# SparkFun_Qwiic_ToF_Imager_-_VL53L5CX_-_M.net
KiCad netlist of a schematic drawn in EAGLE
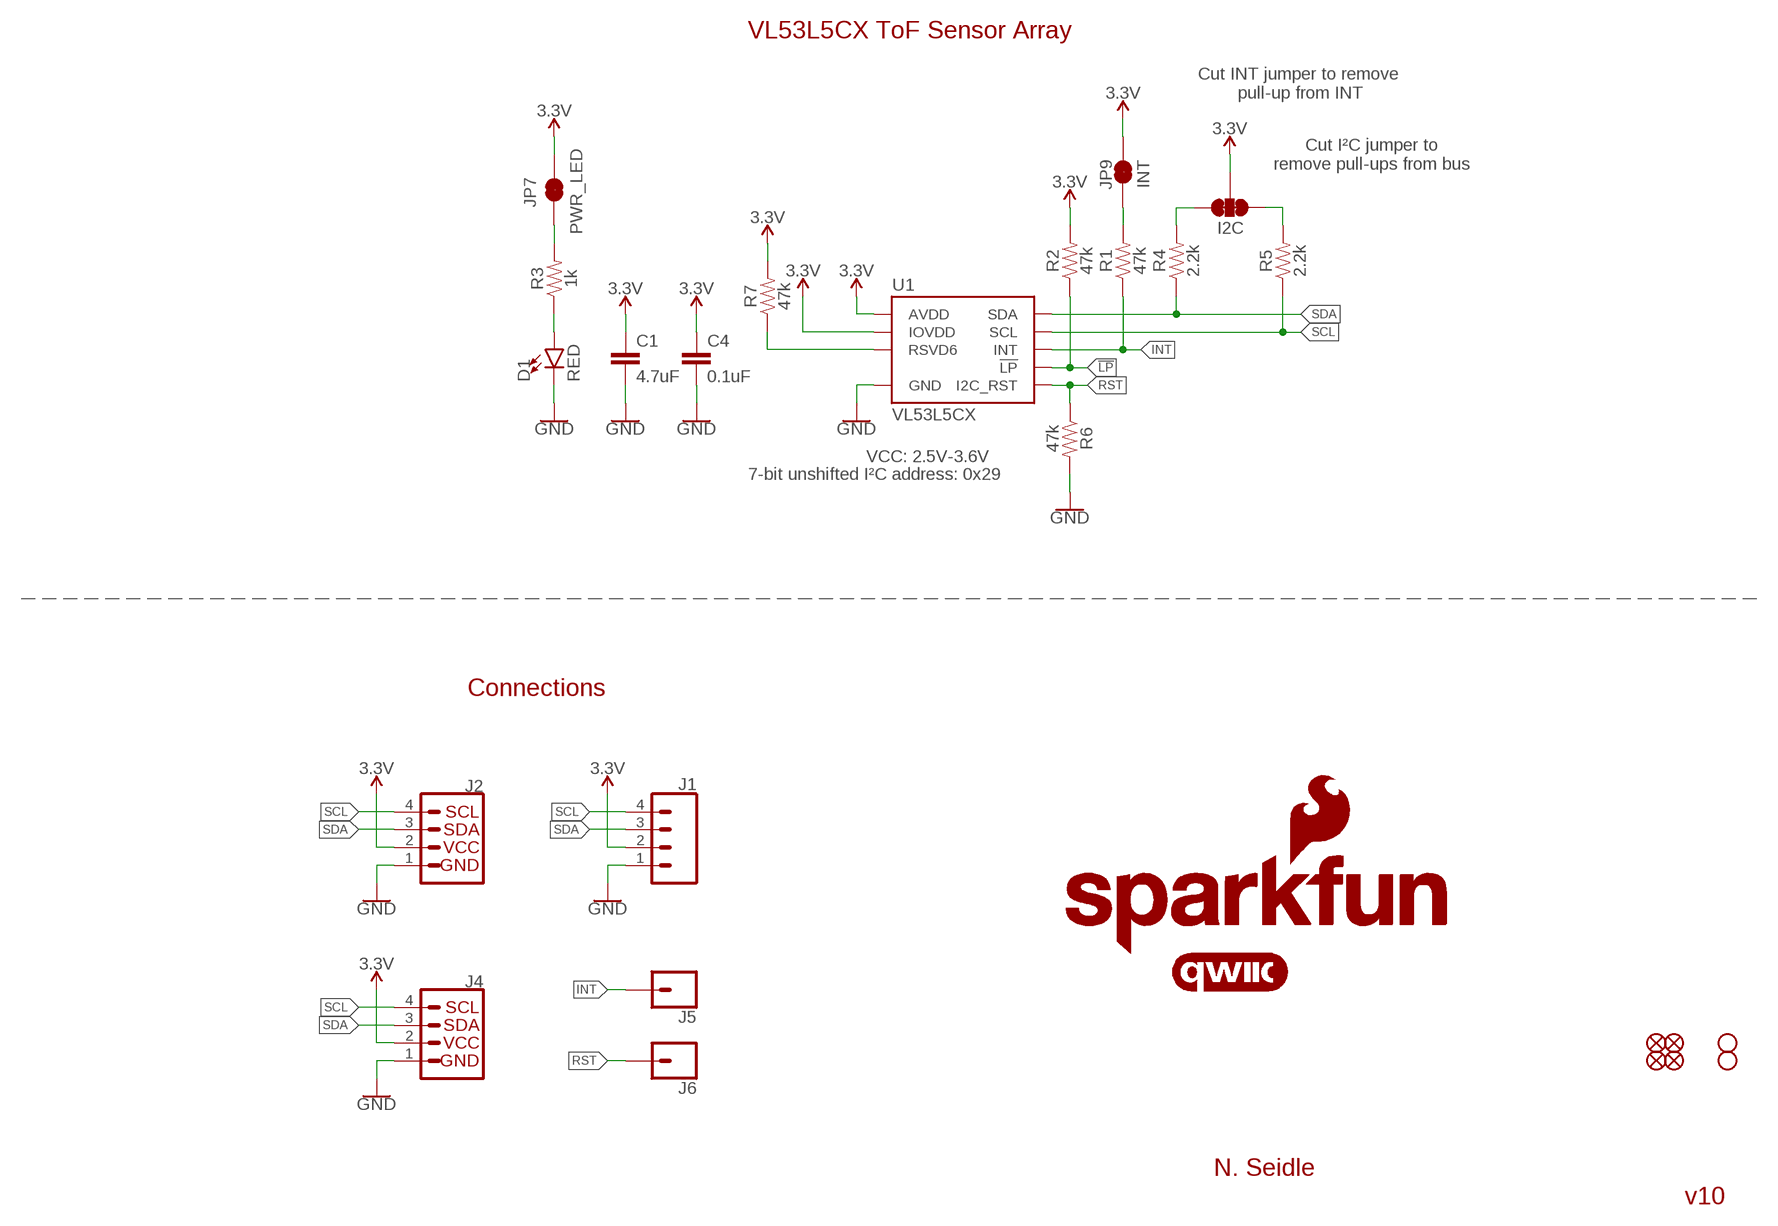
[diagram p0: schematic, sheet 1]

(export (version "E")
  (design (tool "Eeschema 10.0.6"))
  (components
    (comp (ref "C1")
      (value "4.7uF")
      (footprint "eagle-import:0402-TIGHT")
      (libsource (lib "eagle-import") (part "4.7UF-0402_TIGHT-6.3V-20%-X5R"))
    )
    (comp (ref "C4")
      (value "0.1uF")
      (footprint "eagle-import:0402-TIGHT")
      (libsource (lib "eagle-import") (part "0.1UF-0402T-6.3V-10%-X7R"))
    )
    (comp (ref "D1")
      (value "RED")
      (footprint "eagle-import:LED-0603")
      (libsource (lib "eagle-import") (part "LED-RED0603"))
    )
    (comp (ref "I2C")
      (value "JUMPER-SMT_3_2-NC_TRACE_SILK")
      (footprint "eagle-import:SMT-JUMPER_3_2-NC_TRACE_SILK")
      (libsource (lib "eagle-import") (part "JUMPER-SMT_3_2-NC_TRACE_SILK"))
    )
    (comp (ref "J1")
      (value "CONN_041X04_NO_SILK")
      (footprint "eagle-import:1X04_NO_SILK")
      (libsource (lib "eagle-import") (part "CONN_041X04_NO_SILK"))
    )
    (comp (ref "J2")
      (value "Vertical Qwiic Connector")
      (footprint "eagle-import:JST04_1MM_VERT")
      (libsource (lib "eagle-import") (part "QWIIC_CONNECTOR"))
    )
    (comp (ref "J4")
      (value "Vertical Qwiic Connector")
      (footprint "eagle-import:JST04_1MM_VERT")
      (libsource (lib "eagle-import") (part "QWIIC_CONNECTOR"))
    )
    (comp (ref "J5")
      (value "CONN_01PTH_NO_SILK_YES_STOP")
      (footprint "eagle-import:1X01_NO_SILK")
      (libsource (lib "eagle-import") (part "CONN_01PTH_NO_SILK_YES_STOP"))
    )
    (comp (ref "J6")
      (value "CONN_01PTH_NO_SILK_YES_STOP")
      (footprint "eagle-import:1X01_NO_SILK")
      (libsource (lib "eagle-import") (part "CONN_01PTH_NO_SILK_YES_STOP"))
    )
    (comp (ref "JP1")
      (value "FIDUCIALUFIDUCIAL")
      (footprint "eagle-import:FIDUCIAL-MICRO")
      (libsource (lib "eagle-import") (part "FIDUCIALUFIDUCIAL"))
    )
    (comp (ref "JP2")
      (value "FIDUCIALUFIDUCIAL")
      (footprint "eagle-import:FIDUCIAL-MICRO")
      (libsource (lib "eagle-import") (part "FIDUCIALUFIDUCIAL"))
    )
    (comp (ref "JP5")
      (value "FIDUCIALUFIDUCIAL")
      (footprint "eagle-import:FIDUCIAL-MICRO")
      (libsource (lib "eagle-import") (part "FIDUCIALUFIDUCIAL"))
    )
    (comp (ref "JP6")
      (value "FIDUCIALUFIDUCIAL")
      (footprint "eagle-import:FIDUCIAL-MICRO")
      (libsource (lib "eagle-import") (part "FIDUCIALUFIDUCIAL"))
    )
    (comp (ref "JP7")
      (value "PWR_LED")
      (footprint "eagle-import:SMT-JUMPER_2_NC_TRACE_SILK")
      (libsource (lib "eagle-import") (part "JUMPER-SMT_2_NC_TRACE_SILK"))
    )
    (comp (ref "JP9")
      (value "INT")
      (footprint "eagle-import:SMT-JUMPER_2_NC_TRACE_SILK")
      (libsource (lib "eagle-import") (part "JUMPER-SMT_2_NC_TRACE_SILK"))
    )
    (comp (ref "JP10")
      (value "STAND-OFF")
      (footprint "eagle-import:STAND-OFF")
      (libsource (lib "eagle-import") (part "STAND-OFF"))
    )
    (comp (ref "JP11")
      (value "STAND-OFF")
      (footprint "eagle-import:STAND-OFF")
      (libsource (lib "eagle-import") (part "STAND-OFF"))
    )
    (comp (ref "LOGO1")
      (value "SFE_LOGO_NAME_FLAME8_MM")
      (footprint "eagle-import:SFE_LOGO_NAME_FLAME_8MM")
      (libsource (lib "eagle-import") (part "SFE_LOGO_NAME_FLAME8_MM"))
    )
    (comp (ref "LOGO3")
      (value "QWIIC_LOGO_CONNECTOR")
      (footprint "eagle-import:QWIIC_5.5MM")
      (libsource (lib "eagle-import") (part "QWIIC_LOGO_CONNECTOR"))
    )
    (comp (ref "LOGO4")
      (value "SFE_LOGO_NAME6_MM")
      (footprint "eagle-import:SFE_LOGO_NAME_6MM")
      (libsource (lib "eagle-import") (part "SFE_LOGO_NAME6_MM"))
    )
    (comp (ref "R1")
      (value "47k")
      (footprint "eagle-import:0402-TIGHT")
      (libsource (lib "eagle-import") (part "47KOHM-0402-1/10W-1%"))
    )
    (comp (ref "R2")
      (value "47k")
      (footprint "eagle-import:0402-TIGHT")
      (libsource (lib "eagle-import") (part "47KOHM-0402-1/10W-1%"))
    )
    (comp (ref "R3")
      (value "1k")
      (footprint "eagle-import:0402-TIGHT")
      (libsource (lib "eagle-import") (part "1KOHM-0402T-1/16W-1%"))
    )
    (comp (ref "R4")
      (value "2.2k")
      (footprint "eagle-import:0402-TIGHT")
      (libsource (lib "eagle-import") (part "2.2KOHM-0402T-1/16W-1%"))
    )
    (comp (ref "R5")
      (value "2.2k")
      (footprint "eagle-import:0402-TIGHT")
      (libsource (lib "eagle-import") (part "2.2KOHM-0402T-1/16W-1%"))
    )
    (comp (ref "R6")
      (value "47k")
      (footprint "eagle-import:0402-TIGHT")
      (libsource (lib "eagle-import") (part "47KOHM-0402-1/10W-1%"))
    )
    (comp (ref "R7")
      (value "47k")
      (footprint "eagle-import:0402-TIGHT")
      (libsource (lib "eagle-import") (part "47KOHM-0402-1/10W-1%"))
    )
    (comp (ref "U1")
      (value "VL53L5CX")
      (footprint "eagle-import:VL53L5CX")
      (libsource (lib "eagle-import") (part "VL53L5CX"))
    )
  )
  (nets
    (net (code "1") (name "/~{LP}") (class "Default")
      (node (ref "R2") (pin "1") (pinfunction "1_1") (pintype "passive"))
      (node (ref "U1") (pin "A5") (pinfunction "~{LP}_A5") (pintype "bidirectional"))
    )
    (net (code "2") (name "3.3V") (class "Default")
      (node (ref "C1") (pin "1") (pinfunction "1_1") (pintype "passive"))
      (node (ref "C4") (pin "1") (pinfunction "1_1") (pintype "passive"))
      (node (ref "I2C") (pin "2") (pinfunction "2_2") (pintype "passive"))
      (node (ref "J1") (pin "2") (pinfunction "2_2") (pintype "passive"))
      (node (ref "J2") (pin "2") (pinfunction "2_2") (pintype "power_in"))
      (node (ref "J4") (pin "2") (pinfunction "2_2") (pintype "power_in"))
      (node (ref "JP7") (pin "2") (pinfunction "2_2") (pintype "passive"))
      (node (ref "JP9") (pin "2") (pinfunction "2_2") (pintype "passive"))
      (node (ref "R2") (pin "2") (pinfunction "2_2") (pintype "passive"))
      (node (ref "R7") (pin "2") (pinfunction "2_2") (pintype "passive"))
      (node (ref "U1") (pin "A4") (pinfunction "IOVDD_A4") (pintype "bidirectional"))
      (node (ref "U1") (pin "B1") (pinfunction "AVDD_B1") (pintype "bidirectional"))
      (node (ref "U1") (pin "B7") (pinfunction "AVDD_B7") (pintype "bidirectional"))
    )
    (net (code "3") (name "GND") (class "Default")
      (node (ref "C1") (pin "2") (pinfunction "2_2") (pintype "passive"))
      (node (ref "C4") (pin "2") (pinfunction "2_2") (pintype "passive"))
      (node (ref "D1") (pin "C") (pinfunction "C_C") (pintype "passive"))
      (node (ref "J1") (pin "1") (pinfunction "1_1") (pintype "passive"))
      (node (ref "J2") (pin "1") (pinfunction "1_1") (pintype "power_in"))
      (node (ref "J4") (pin "1") (pinfunction "1_1") (pintype "power_in"))
      (node (ref "R6") (pin "2") (pinfunction "2_2") (pintype "passive"))
      (node (ref "U1") (pin "A2") (pinfunction "GND_A2") (pintype "bidirectional"))
      (node (ref "U1") (pin "A6") (pinfunction "GND_A6") (pintype "bidirectional"))
      (node (ref "U1") (pin "A7") (pinfunction "GND_A7") (pintype "bidirectional"))
      (node (ref "U1") (pin "B4") (pinfunction "GND_B4") (pintype "bidirectional"))
      (node (ref "U1") (pin "C1") (pinfunction "GND_C1") (pintype "bidirectional"))
      (node (ref "U1") (pin "C6") (pinfunction "GND_C6") (pintype "bidirectional"))
      (node (ref "U1") (pin "C7") (pinfunction "GND_C7") (pintype "bidirectional"))
    )
    (net (code "4") (name "INT") (class "Default")
      (node (ref "J5") (pin "1") (pinfunction "1_1") (pintype "passive"))
      (node (ref "R1") (pin "1") (pinfunction "1_1") (pintype "passive"))
      (node (ref "U1") (pin "A3") (pinfunction "INT_A3") (pintype "bidirectional"))
    )
    (net (code "5") (name "Net-(D1-PadA)") (class "Default")
      (node (ref "D1") (pin "A") (pinfunction "A_A") (pintype "passive"))
      (node (ref "R3") (pin "1") (pinfunction "1_1") (pintype "passive"))
    )
    (net (code "6") (name "Net-(I2C-Pad1)") (class "Default")
      (node (ref "I2C") (pin "1") (pinfunction "1_1") (pintype "passive"))
      (node (ref "R5") (pin "2") (pinfunction "2_2") (pintype "passive"))
    )
    (net (code "7") (name "Net-(I2C-Pad3)") (class "Default")
      (node (ref "I2C") (pin "3") (pinfunction "3_3") (pintype "passive"))
      (node (ref "R4") (pin "2") (pinfunction "2_2") (pintype "passive"))
    )
    (net (code "8") (name "Net-(JP7-Pad1)") (class "Default")
      (node (ref "JP7") (pin "1") (pinfunction "1_1") (pintype "passive"))
      (node (ref "R3") (pin "2") (pinfunction "2_2") (pintype "passive"))
    )
    (net (code "9") (name "Net-(JP9-Pad1)") (class "Default")
      (node (ref "JP9") (pin "1") (pinfunction "1_1") (pintype "passive"))
      (node (ref "R1") (pin "2") (pinfunction "2_2") (pintype "passive"))
    )
    (net (code "10") (name "Net-(U1-RSVD6)") (class "Default")
      (node (ref "R7") (pin "1") (pinfunction "1_1") (pintype "passive"))
      (node (ref "U1") (pin "C2") (pinfunction "RSVD6_C2") (pintype "bidirectional"))
    )
    (net (code "11") (name "RST") (class "Default")
      (node (ref "J6") (pin "1") (pinfunction "1_1") (pintype "passive"))
      (node (ref "R6") (pin "1") (pinfunction "1_1") (pintype "passive"))
      (node (ref "U1") (pin "A1") (pinfunction "I2C_RST_A1") (pintype "bidirectional"))
    )
    (net (code "12") (name "SCL") (class "Default")
      (node (ref "J1") (pin "4") (pinfunction "4_4") (pintype "passive"))
      (node (ref "J2") (pin "4") (pinfunction "4_4") (pintype "passive"))
      (node (ref "J4") (pin "4") (pinfunction "4_4") (pintype "passive"))
      (node (ref "R5") (pin "1") (pinfunction "1_1") (pintype "passive"))
      (node (ref "U1") (pin "C4") (pinfunction "SCL_C4") (pintype "bidirectional"))
    )
    (net (code "13") (name "SDA") (class "Default")
      (node (ref "J1") (pin "3") (pinfunction "3_3") (pintype "passive"))
      (node (ref "J2") (pin "3") (pinfunction "3_3") (pintype "passive"))
      (node (ref "J4") (pin "3") (pinfunction "3_3") (pintype "passive"))
      (node (ref "R4") (pin "1") (pinfunction "1_1") (pintype "passive"))
      (node (ref "U1") (pin "C3") (pinfunction "SDA_C3") (pintype "bidirectional"))
    )
  )
)
